# romcart_8k.net
KiCad netlist of a schematic drawn in EAGLE
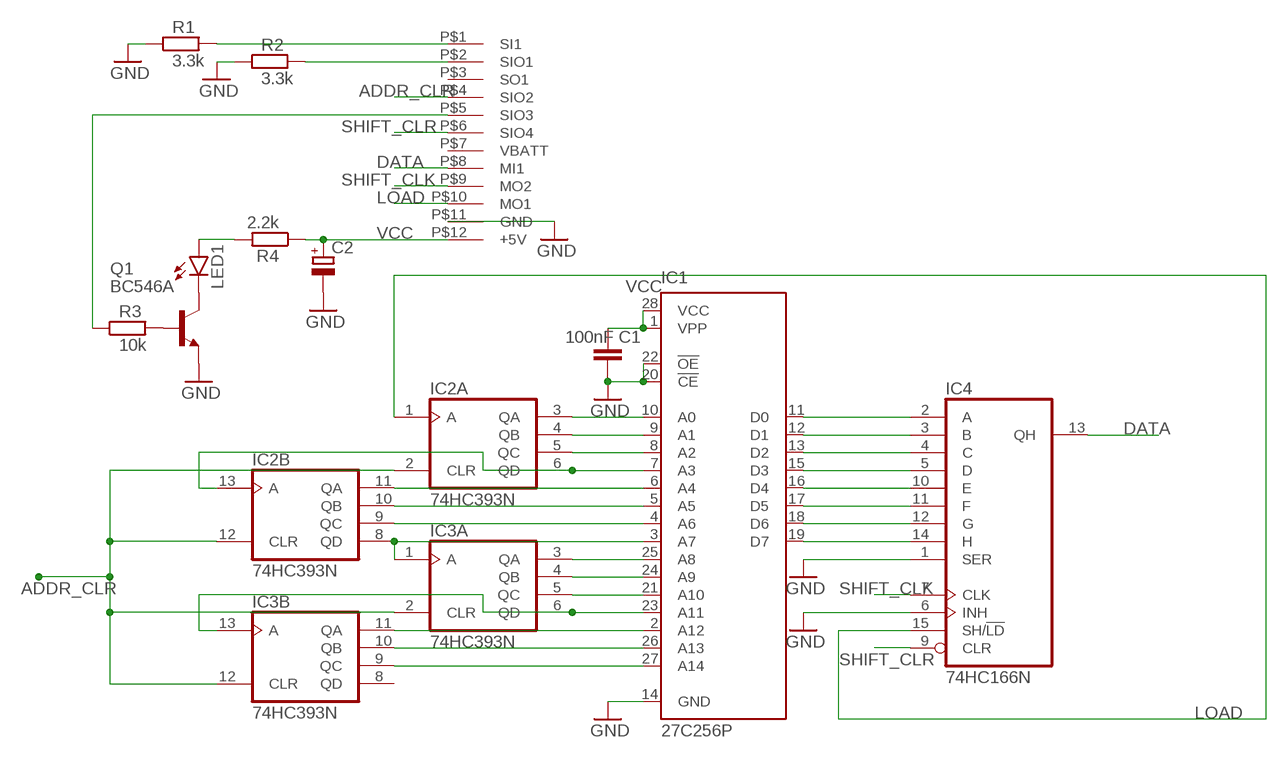
[diagram p0: schematic, sheet 1]

(export (version "E")
  (design (tool "Eeschema 10.0.6"))
  (components
    (comp (ref "C1")
      (value "100nF")
      (footprint "eagle-import:C2.5-3")
      (libsource (lib "eagle-import") (part "C2,5-3"))
    )
    (comp (ref "C2")
      (value "CPOL-EUE3.5-8")
      (footprint "eagle-import:E3,5-8")
      (libsource (lib "eagle-import") (part "CPOL-EUE3.5-8"))
    )
    (comp (ref "IC1")
      (value "27C256P")
      (footprint "eagle-import:DIL28-6")
      (fields (field (name "MF") "Arrow Electronics") (field (name "MPN") "M27C256B15F1"))
      (libsource (lib "eagle-import") (part "27256PC"))
    )
    (comp (ref "IC2")
      (value "74HC393N")
      (footprint "eagle-import:DIL14")
      (libsource (lib "eagle-import") (part "74393NHC"))
    )
    (comp (ref "IC3")
      (value "74HC393N")
      (footprint "eagle-import:DIL14")
      (libsource (lib "eagle-import") (part "74393NHC"))
    )
    (comp (ref "IC4")
      (value "74HC166N")
      (footprint "eagle-import:DIL16")
      (libsource (lib "eagle-import") (part "74166NHC"))
    )
    (comp (ref "LED1")
      (value "LED3MM")
      (footprint "eagle-import:LED3MM")
      (libsource (lib "eagle-import") (part "LED3MM"))
    )
    (comp (ref "Q1")
      (value "BC546A")
      (footprint "eagle-import:TO92-EBC")
      (libsource (lib "eagle-import") (part "BC546A"))
    )
    (comp (ref "R1")
      (value "3.3k")
      (footprint "eagle-import:0204_5")
      (libsource (lib "eagle-import") (part "R-EU_0204/5"))
    )
    (comp (ref "R2")
      (value "3.3k")
      (footprint "eagle-import:0204_5")
      (libsource (lib "eagle-import") (part "R-EU_0204/5"))
    )
    (comp (ref "R3")
      (value "10k")
      (footprint "eagle-import:0204_5")
      (libsource (lib "eagle-import") (part "R-EU_0204/5"))
    )
    (comp (ref "R4")
      (value "2.2k")
      (footprint "eagle-import:0204_5")
      (libsource (lib "eagle-import") (part "R-EU_0204/5"))
    )
    (comp (ref "U$1")
      (value "HX20_CASSETTE")
      (footprint "eagle-import:HX20_CASSETTE")
      (libsource (lib "eagle-import") (part "HX20_CASSETTE"))
    )
  )
  (nets
    (net (code "1") (name "/ADDR_CLR") (class "Default")
      (node (ref "IC2") (pin "12") (pinfunction "CLR_12") (pintype "input"))
      (node (ref "IC2") (pin "2") (pinfunction "CLR_2") (pintype "input"))
      (node (ref "IC3") (pin "12") (pinfunction "CLR_12") (pintype "input"))
      (node (ref "IC3") (pin "2") (pinfunction "CLR_2") (pintype "input"))
      (node (ref "U$1") (pin "P$4") (pinfunction "SIO2_P$4") (pintype "bidirectional"))
    )
    (net (code "2") (name "/DATA") (class "Default")
      (node (ref "IC4") (pin "13") (pinfunction "QH_13") (pintype "output"))
      (node (ref "U$1") (pin "P$8") (pinfunction "MI1_P$8") (pintype "bidirectional"))
    )
    (net (code "3") (name "/LOAD") (class "Default")
      (node (ref "IC2") (pin "1") (pinfunction "A_1") (pintype "input"))
      (node (ref "IC4") (pin "15") (pinfunction "SH/~{LD}_15") (pintype "input"))
      (node (ref "U$1") (pin "P$10") (pinfunction "MO1_P$10") (pintype "bidirectional"))
    )
    (net (code "4") (name "/SHIFT_CLK") (class "Default")
      (node (ref "IC4") (pin "7") (pinfunction "CLK_7") (pintype "input"))
      (node (ref "U$1") (pin "P$9") (pinfunction "MO2_P$9") (pintype "bidirectional"))
    )
    (net (code "5") (name "/SHIFT_CLR") (class "Default")
      (node (ref "IC4") (pin "9") (pinfunction "CLR_9") (pintype "input"))
      (node (ref "U$1") (pin "P$6") (pinfunction "SIO4_P$6") (pintype "bidirectional"))
    )
    (net (code "6") (name "/VCC") (class "Default")
      (node (ref "C1") (pin "1") (pinfunction "1_1") (pintype "passive"))
      (node (ref "C2") (pin "+") (pinfunction "+_+") (pintype "passive"))
      (node (ref "IC1") (pin "1") (pinfunction "VPP_1") (pintype "input"))
      (node (ref "IC1") (pin "28") (pinfunction "VCC_28") (pintype "power_in"))
      (node (ref "R4") (pin "1") (pinfunction "1_1") (pintype "passive"))
      (node (ref "U$1") (pin "P$12") (pinfunction "+5V_P$12") (pintype "bidirectional"))
    )
    (net (code "7") (name "GND") (class "Default")
      (node (ref "C1") (pin "2") (pinfunction "2_2") (pintype "passive"))
      (node (ref "C2") (pin "-") (pinfunction "-_-") (pintype "passive"))
      (node (ref "IC1") (pin "14") (pinfunction "GND_14") (pintype "power_in"))
      (node (ref "IC1") (pin "20") (pinfunction "~{CE}_20") (pintype "input"))
      (node (ref "IC1") (pin "22") (pinfunction "~{OE}_22") (pintype "input"))
      (node (ref "IC4") (pin "1") (pinfunction "SER_1") (pintype "input"))
      (node (ref "IC4") (pin "6") (pinfunction "INH_6") (pintype "input"))
      (node (ref "Q1") (pin "E") (pinfunction "E_E") (pintype "passive"))
      (node (ref "R1") (pin "1") (pinfunction "1_1") (pintype "passive"))
      (node (ref "R2") (pin "1") (pinfunction "1_1") (pintype "passive"))
      (node (ref "U$1") (pin "P$11") (pinfunction "GND_P$11") (pintype "bidirectional"))
    )
    (net (code "8") (name "Net-(IC1-A0)") (class "Default")
      (node (ref "IC1") (pin "10") (pinfunction "A0_10") (pintype "input"))
      (node (ref "IC2") (pin "3") (pinfunction "QA_3") (pintype "output"))
    )
    (net (code "9") (name "Net-(IC1-A1)") (class "Default")
      (node (ref "IC1") (pin "9") (pinfunction "A1_9") (pintype "input"))
      (node (ref "IC2") (pin "4") (pinfunction "QB_4") (pintype "output"))
    )
    (net (code "10") (name "Net-(IC1-A2)") (class "Default")
      (node (ref "IC1") (pin "8") (pinfunction "A2_8") (pintype "input"))
      (node (ref "IC2") (pin "5") (pinfunction "QC_5") (pintype "output"))
    )
    (net (code "11") (name "Net-(IC1-A3)") (class "Default")
      (node (ref "IC1") (pin "7") (pinfunction "A3_7") (pintype "input"))
      (node (ref "IC2") (pin "13") (pinfunction "A_13") (pintype "input"))
      (node (ref "IC2") (pin "6") (pinfunction "QD_6") (pintype "output"))
    )
    (net (code "12") (name "Net-(IC1-A4)") (class "Default")
      (node (ref "IC1") (pin "6") (pinfunction "A4_6") (pintype "input"))
      (node (ref "IC2") (pin "11") (pinfunction "QA_11") (pintype "output"))
    )
    (net (code "13") (name "Net-(IC1-A5)") (class "Default")
      (node (ref "IC1") (pin "5") (pinfunction "A5_5") (pintype "input"))
      (node (ref "IC2") (pin "10") (pinfunction "QB_10") (pintype "output"))
    )
    (net (code "14") (name "Net-(IC1-A6)") (class "Default")
      (node (ref "IC1") (pin "4") (pinfunction "A6_4") (pintype "input"))
      (node (ref "IC2") (pin "9") (pinfunction "QC_9") (pintype "output"))
    )
    (net (code "15") (name "Net-(IC1-A7)") (class "Default")
      (node (ref "IC1") (pin "3") (pinfunction "A7_3") (pintype "input"))
      (node (ref "IC2") (pin "8") (pinfunction "QD_8") (pintype "output"))
      (node (ref "IC3") (pin "1") (pinfunction "A_1") (pintype "input"))
    )
    (net (code "16") (name "Net-(IC1-A8)") (class "Default")
      (node (ref "IC1") (pin "25") (pinfunction "A8_25") (pintype "input"))
      (node (ref "IC3") (pin "3") (pinfunction "QA_3") (pintype "output"))
    )
    (net (code "17") (name "Net-(IC1-A9)") (class "Default")
      (node (ref "IC1") (pin "24") (pinfunction "A9_24") (pintype "input"))
      (node (ref "IC3") (pin "4") (pinfunction "QB_4") (pintype "output"))
    )
    (net (code "18") (name "Net-(IC1-A10)") (class "Default")
      (node (ref "IC1") (pin "21") (pinfunction "A10_21") (pintype "input"))
      (node (ref "IC3") (pin "5") (pinfunction "QC_5") (pintype "output"))
    )
    (net (code "19") (name "Net-(IC1-A11)") (class "Default")
      (node (ref "IC1") (pin "23") (pinfunction "A11_23") (pintype "input"))
      (node (ref "IC3") (pin "13") (pinfunction "A_13") (pintype "input"))
      (node (ref "IC3") (pin "6") (pinfunction "QD_6") (pintype "output"))
    )
    (net (code "20") (name "Net-(IC1-A12)") (class "Default")
      (node (ref "IC1") (pin "2") (pinfunction "A12_2") (pintype "input"))
      (node (ref "IC3") (pin "11") (pinfunction "QA_11") (pintype "output"))
    )
    (net (code "21") (name "Net-(IC1-A13)") (class "Default")
      (node (ref "IC1") (pin "26") (pinfunction "A13_26") (pintype "input"))
      (node (ref "IC3") (pin "10") (pinfunction "QB_10") (pintype "output"))
    )
    (net (code "22") (name "Net-(IC1-A14)") (class "Default")
      (node (ref "IC1") (pin "27") (pinfunction "A14_27") (pintype "input"))
      (node (ref "IC3") (pin "9") (pinfunction "QC_9") (pintype "output"))
    )
    (net (code "23") (name "Net-(IC1-D0)") (class "Default")
      (node (ref "IC1") (pin "11") (pinfunction "D0_11") (pintype "tri_state"))
      (node (ref "IC4") (pin "2") (pinfunction "A_2") (pintype "input"))
    )
    (net (code "24") (name "Net-(IC1-D1)") (class "Default")
      (node (ref "IC1") (pin "12") (pinfunction "D1_12") (pintype "tri_state"))
      (node (ref "IC4") (pin "3") (pinfunction "B_3") (pintype "input"))
    )
    (net (code "25") (name "Net-(IC1-D2)") (class "Default")
      (node (ref "IC1") (pin "13") (pinfunction "D2_13") (pintype "tri_state"))
      (node (ref "IC4") (pin "4") (pinfunction "C_4") (pintype "input"))
    )
    (net (code "26") (name "Net-(IC1-D3)") (class "Default")
      (node (ref "IC1") (pin "15") (pinfunction "D3_15") (pintype "tri_state"))
      (node (ref "IC4") (pin "5") (pinfunction "D_5") (pintype "input"))
    )
    (net (code "27") (name "Net-(IC1-D4)") (class "Default")
      (node (ref "IC1") (pin "16") (pinfunction "D4_16") (pintype "tri_state"))
      (node (ref "IC4") (pin "10") (pinfunction "E_10") (pintype "input"))
    )
    (net (code "28") (name "Net-(IC1-D5)") (class "Default")
      (node (ref "IC1") (pin "17") (pinfunction "D5_17") (pintype "tri_state"))
      (node (ref "IC4") (pin "11") (pinfunction "F_11") (pintype "input"))
    )
    (net (code "29") (name "Net-(IC1-D6)") (class "Default")
      (node (ref "IC1") (pin "18") (pinfunction "D6_18") (pintype "tri_state"))
      (node (ref "IC4") (pin "12") (pinfunction "G_12") (pintype "input"))
    )
    (net (code "30") (name "Net-(IC1-D7)") (class "Default")
      (node (ref "IC1") (pin "19") (pinfunction "D7_19") (pintype "tri_state"))
      (node (ref "IC4") (pin "14") (pinfunction "H_14") (pintype "input"))
    )
    (net (code "31") (name "Net-(LED1-C)") (class "Default")
      (node (ref "LED1") (pin "K") (pinfunction "C_K") (pintype "passive"))
      (node (ref "Q1") (pin "C") (pinfunction "C_C") (pintype "passive"))
    )
    (net (code "32") (name "Net-(LED1-PadA)") (class "Default")
      (node (ref "LED1") (pin "A") (pinfunction "A_A") (pintype "passive"))
      (node (ref "R4") (pin "2") (pinfunction "2_2") (pintype "passive"))
    )
    (net (code "33") (name "Net-(Q1-PadB)") (class "Default")
      (node (ref "Q1") (pin "B") (pinfunction "B_B") (pintype "passive"))
      (node (ref "R3") (pin "2") (pinfunction "2_2") (pintype "passive"))
    )
    (net (code "34") (name "Net-(U$1-SI1)") (class "Default")
      (node (ref "R1") (pin "2") (pinfunction "2_2") (pintype "passive"))
      (node (ref "U$1") (pin "P$1") (pinfunction "SI1_P$1") (pintype "bidirectional"))
    )
    (net (code "35") (name "Net-(U$1-SIO1)") (class "Default")
      (node (ref "R2") (pin "2") (pinfunction "2_2") (pintype "passive"))
      (node (ref "U$1") (pin "P$2") (pinfunction "SIO1_P$2") (pintype "bidirectional"))
    )
    (net (code "36") (name "Net-(U$1-SIO3)") (class "Default")
      (node (ref "R3") (pin "1") (pinfunction "1_1") (pintype "passive"))
      (node (ref "U$1") (pin "P$5") (pinfunction "SIO3_P$5") (pintype "bidirectional"))
    )
    (net (code "37") (name "unconnected-(IC3B-QD-Pad8)") (class "Default")
      (node (ref "IC3") (pin "8") (pinfunction "QD_8") (pintype "output"))
    )
    (net (code "38") (name "unconnected-(U$1-SO1-PadP$3)") (class "Default")
      (node (ref "U$1") (pin "P$3") (pinfunction "SO1_P$3") (pintype "bidirectional"))
    )
    (net (code "39") (name "unconnected-(U$1-VBATT-PadP$7)") (class "Default")
      (node (ref "U$1") (pin "P$7") (pinfunction "VBATT_P$7") (pintype "bidirectional"))
    )
  )
)
